# 01_POWER.net
KiCad netlist of a schematic drawn in Altium Designer
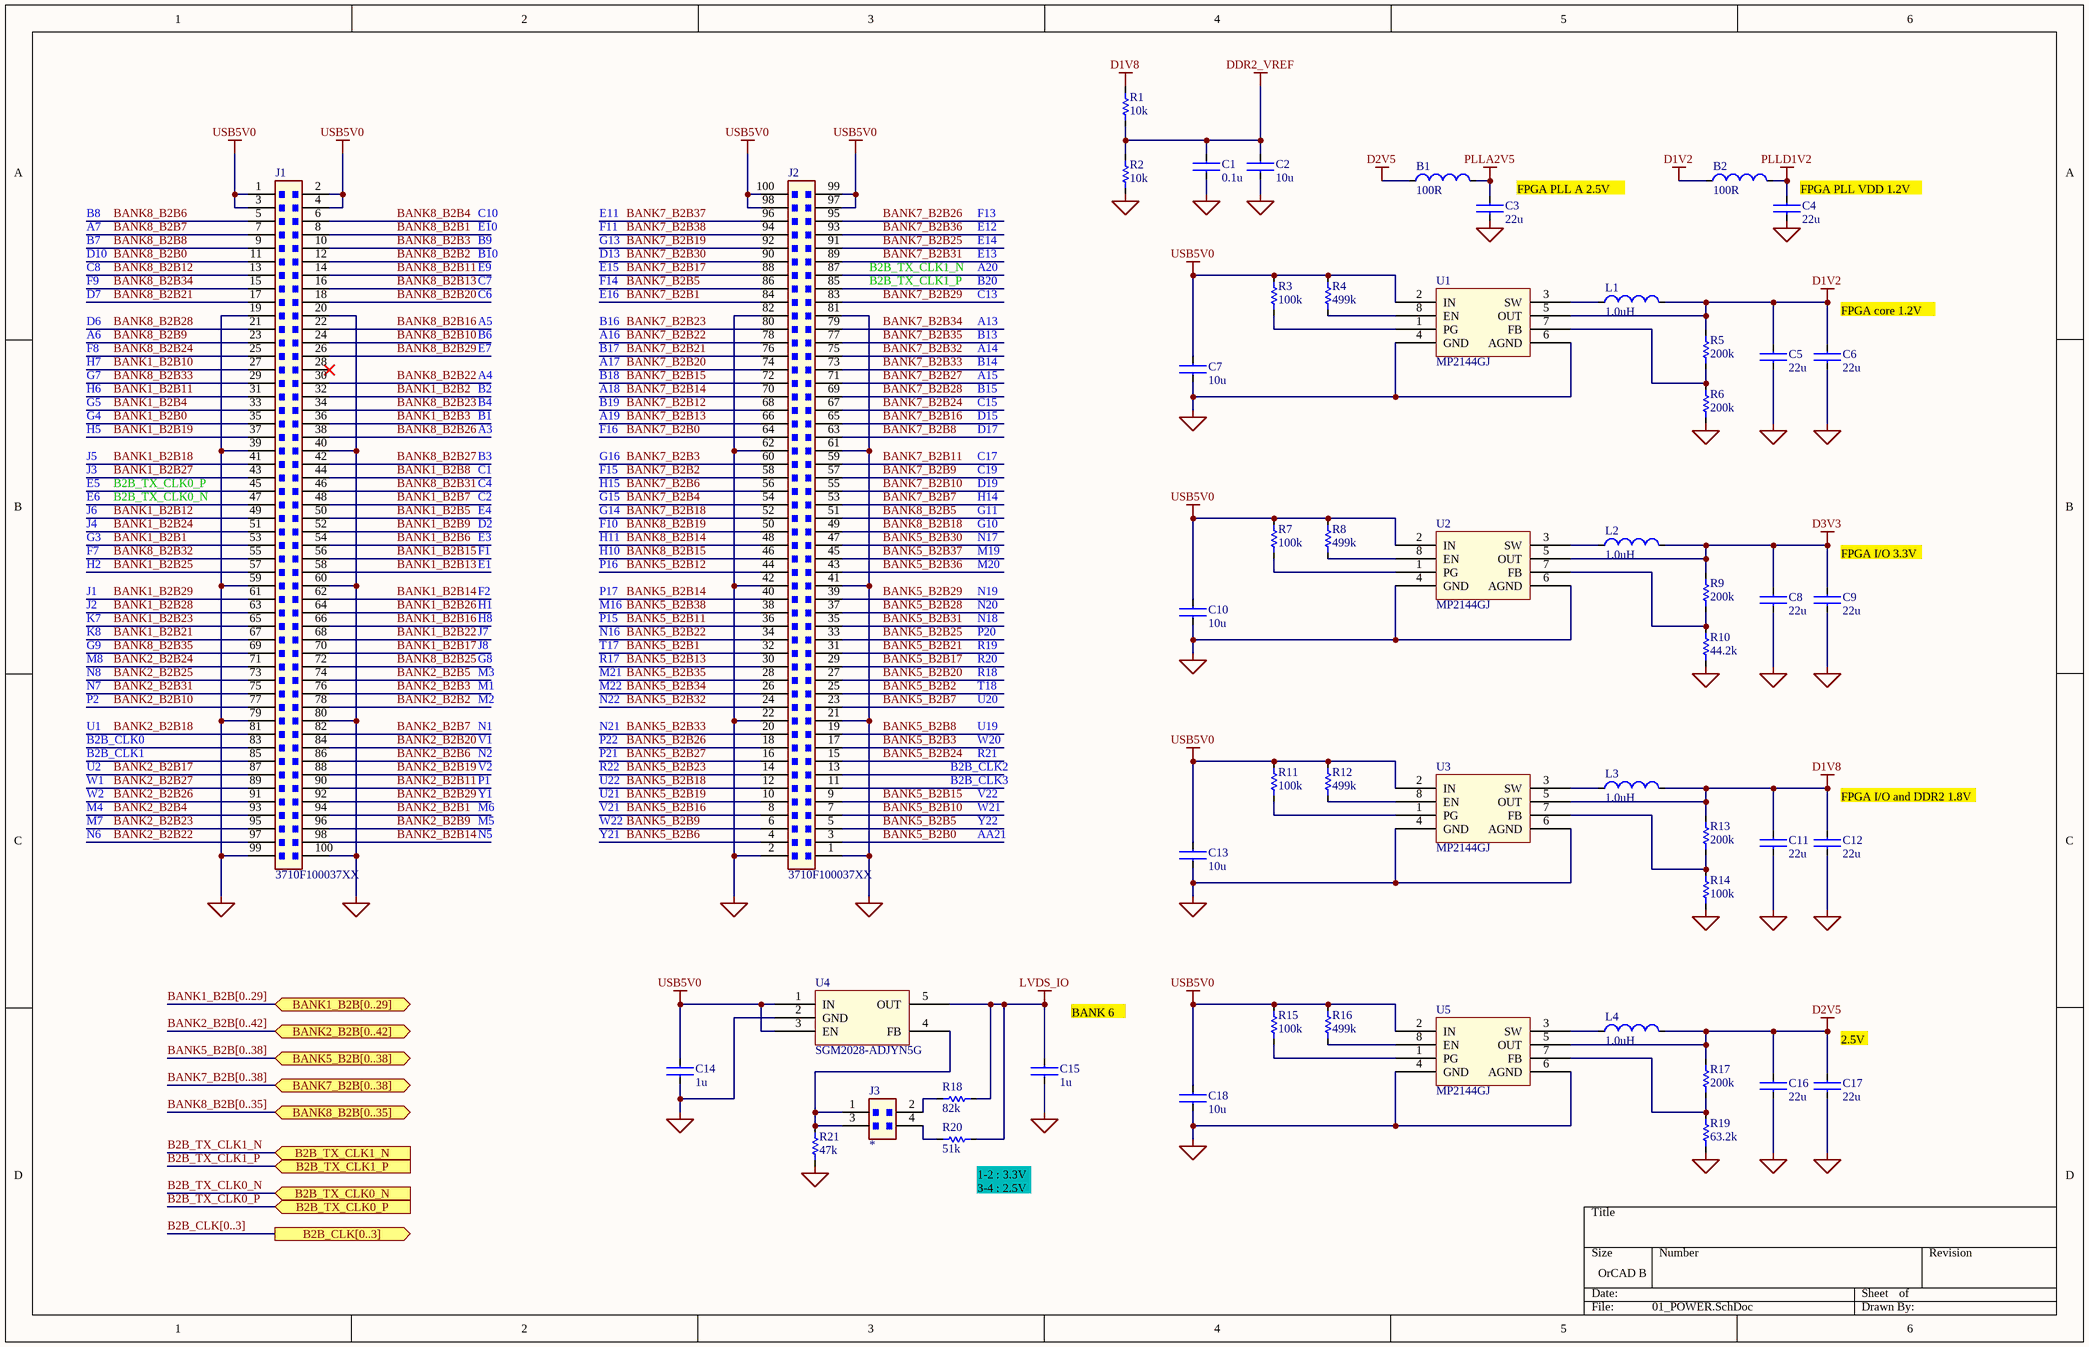
[diagram p0: 01_POWER.SchDoc]

(export (version "E")
  (design (tool "Eeschema 10.0.6"))
  (components
    (comp (ref "B1")
      (value "100R")
      (footprint "INDC1608X09N_B0603_TAIYO")
      (description "Bead,100R,2500mA,0.035ohm,0603")
      (libsource (lib "AD15_libpkg") (part "FBMH1608HM101-T"))
    )
    (comp (ref "B2")
      (value "100R")
      (footprint "INDC1608X09N_B0603_TAIYO")
      (description "Bead,100R,2500mA,0.035ohm,0603")
      (libsource (lib "AD15_libpkg") (part "FBMH1608HM101-T"))
    )
    (comp (ref "C1")
      (value "0.1u")
      (footprint "C0402")
      (description "CAP,Ceramic,X7R,10%,16V,0.1uF,0402")
      (libsource (lib "C0402") (part "CAP011"))
    )
    (comp (ref "C2")
      (value "10u")
      (footprint "CAPC1608X09N_C0603")
      (description "CAP,Ceramic,X7R,10%,6.3V,10uF,0603")
      (libsource (lib "C0603") (part "CAP113"))
    )
    (comp (ref "C3")
      (value "22u")
      (footprint "CAPC1608X09N_C0603")
      (description "CAP,Ceramic,X7R,10%,6.3V,22uF,0603")
      (libsource (lib "C0603") (part "CAP114"))
    )
    (comp (ref "C4")
      (value "22u")
      (footprint "CAPC1608X09N_C0603")
      (description "CAP,Ceramic,X7R,10%,6.3V,22uF,0603")
      (libsource (lib "C0603") (part "CAP114"))
    )
    (comp (ref "C5")
      (value "22u")
      (footprint "CAPC1608X09N_C0603")
      (description "CAP,Ceramic,X7R,10%,6.3V,22uF,0603")
      (libsource (lib "C0603") (part "CAP114"))
    )
    (comp (ref "C6")
      (value "22u")
      (footprint "CAPC1608X09N_C0603")
      (description "CAP,Ceramic,X7R,10%,6.3V,22uF,0603")
      (libsource (lib "C0603") (part "CAP114"))
    )
    (comp (ref "C7")
      (value "10u")
      (footprint "CAPC1608X09N_C0603")
      (description "CAP,Ceramic,X7R,10%,6.3V,10uF,0603")
      (libsource (lib "C0603") (part "CAP113"))
    )
    (comp (ref "C8")
      (value "22u")
      (footprint "CAPC1608X09N_C0603")
      (description "CAP,Ceramic,X7R,10%,6.3V,22uF,0603")
      (libsource (lib "C0603") (part "CAP114"))
    )
    (comp (ref "C9")
      (value "22u")
      (footprint "CAPC1608X09N_C0603")
      (description "CAP,Ceramic,X7R,10%,6.3V,22uF,0603")
      (libsource (lib "C0603") (part "CAP114"))
    )
    (comp (ref "C10")
      (value "10u")
      (footprint "CAPC1608X09N_C0603")
      (description "CAP,Ceramic,X7R,10%,6.3V,10uF,0603")
      (libsource (lib "C0603") (part "CAP113"))
    )
    (comp (ref "C11")
      (value "22u")
      (footprint "CAPC1608X09N_C0603")
      (description "CAP,Ceramic,X7R,10%,6.3V,22uF,0603")
      (libsource (lib "C0603") (part "CAP114"))
    )
    (comp (ref "C12")
      (value "22u")
      (footprint "CAPC1608X09N_C0603")
      (description "CAP,Ceramic,X7R,10%,6.3V,22uF,0603")
      (libsource (lib "C0603") (part "CAP114"))
    )
    (comp (ref "C13")
      (value "10u")
      (footprint "CAPC1608X09N_C0603")
      (description "CAP,Ceramic,X7R,10%,6.3V,10uF,0603")
      (libsource (lib "C0603") (part "CAP113"))
    )
    (comp (ref "C14")
      (value "1u")
      (footprint "CAPC1608X09N_C0603")
      (description "CAP,Ceramic,X7R,10%,16V,1uF,0603")
      (libsource (lib "AD15_libpkg") (part "CAP12"))
    )
    (comp (ref "C15")
      (value "1u")
      (footprint "CAPC1608X09N_C0603")
      (description "CAP,Ceramic,X7R,10%,16V,1uF,0603")
      (libsource (lib "AD15_libpkg") (part "CAP12"))
    )
    (comp (ref "C16")
      (value "22u")
      (footprint "CAPC1608X09N_C0603")
      (description "CAP,Ceramic,X7R,10%,6.3V,22uF,0603")
      (libsource (lib "C0603") (part "CAP114"))
    )
    (comp (ref "C17")
      (value "22u")
      (footprint "CAPC1608X09N_C0603")
      (description "CAP,Ceramic,X7R,10%,6.3V,22uF,0603")
      (libsource (lib "C0603") (part "CAP114"))
    )
    (comp (ref "C18")
      (value "10u")
      (footprint "CAPC1608X09N_C0603")
      (description "CAP,Ceramic,X7R,10%,6.3V,10uF,0603")
      (libsource (lib "C0603") (part "CAP113"))
    )
    (comp (ref "J1")
      (value "3710F100037XX")
      (footprint "3710F100037XX")
      (description "B2B female,100Pin,Vertical,0.8mm Pitch,SMD")
      (libsource (lib "AD15_schlib") (part "3710F100037XX"))
    )
    (comp (ref "J2")
      (value "3710F100037XX")
      (footprint "3710F100037XX")
      (description "B2B female,100Pin,Vertical,0.8mm Pitch,SMD")
      (libsource (lib "AD15_schlib") (part "3710F100037XX"))
    )
    (comp (ref "J3")
      (value "*")
      (footprint "334202XX30000")
      (description "Header,4Pin,Vertical,1.27mm Pitch,SMD")
      (libsource (lib "AD15_schlib") (part "334202XX30000"))
    )
    (comp (ref "L1")
      (value "1.0uH")
      (footprint "NR3015T1R0N")
      (description "Inductor,1.0uH,2100mA,0.03ohm,SMD")
      (libsource (lib "AD15_schlib") (part "NR3015T1R0N"))
    )
    (comp (ref "L2")
      (value "1.0uH")
      (footprint "NR3015T1R0N")
      (description "Inductor,1.0uH,2100mA,0.03ohm,SMD")
      (libsource (lib "AD15_schlib") (part "NR3015T1R0N"))
    )
    (comp (ref "L3")
      (value "1.0uH")
      (footprint "NR3015T1R0N")
      (description "Inductor,1.0uH,2100mA,0.03ohm,SMD")
      (libsource (lib "AD15_schlib") (part "NR3015T1R0N"))
    )
    (comp (ref "L4")
      (value "1.0uH")
      (footprint "NR3015T1R0N")
      (description "Inductor,1.0uH,2100mA,0.03ohm,SMD")
      (libsource (lib "AD15_schlib") (part "NR3015T1R0N"))
    )
    (comp (ref "R1")
      (value "10k")
      (footprint "R0402")
      (description "RES,10k,1%,1/16W,0402")
      (libsource (lib "R0402") (part "RES012"))
    )
    (comp (ref "R2")
      (value "10k")
      (footprint "R0402")
      (description "RES,10k,1%,1/16W,0402")
      (libsource (lib "R0402") (part "RES012"))
    )
    (comp (ref "R3")
      (value "100k")
      (footprint "R0402")
      (description "RES,100k,1%,1/16W,0402")
      (libsource (lib "R0402") (part "RES013"))
    )
    (comp (ref "R4")
      (value "499k")
      (footprint "R0402")
      (description "RES,499k,1%,1/16W,0402")
      (libsource (lib "R0402") (part "RES0117_1"))
    )
    (comp (ref "R5")
      (value "200k")
      (footprint "R0402")
      (description "RES,200k,1%,1/16W,0402")
      (libsource (lib "R0402") (part "RES0117"))
    )
    (comp (ref "R6")
      (value "200k")
      (footprint "R0402")
      (description "RES,200k,1%,1/16W,0402")
      (libsource (lib "R0402") (part "RES0117"))
    )
    (comp (ref "R7")
      (value "100k")
      (footprint "R0402")
      (description "RES,100k,1%,1/16W,0402")
      (libsource (lib "R0402") (part "RES013"))
    )
    (comp (ref "R8")
      (value "499k")
      (footprint "R0402")
      (description "RES,499k,1%,1/16W,0402")
      (libsource (lib "R0402") (part "RES0117_1"))
    )
    (comp (ref "R9")
      (value "200k")
      (footprint "R0402")
      (description "RES,200k,1%,1/16W,0402")
      (libsource (lib "R0402") (part "RES0117"))
    )
    (comp (ref "R10")
      (value "44.2k")
      (footprint "R0402")
      (description "RES,44.2k,1%,1/16W,0402")
      (libsource (lib "R0402") (part "RES0124_1"))
    )
    (comp (ref "R11")
      (value "100k")
      (footprint "R0402")
      (description "RES,100k,1%,1/16W,0402")
      (libsource (lib "R0402") (part "RES013"))
    )
    (comp (ref "R12")
      (value "499k")
      (footprint "R0402")
      (description "RES,499k,1%,1/16W,0402")
      (libsource (lib "R0402") (part "RES0117_1"))
    )
    (comp (ref "R13")
      (value "200k")
      (footprint "R0402")
      (description "RES,200k,1%,1/16W,0402")
      (libsource (lib "R0402") (part "RES0117"))
    )
    (comp (ref "R14")
      (value "100k")
      (footprint "R0402")
      (description "RES,100k,1%,1/16W,0402")
      (libsource (lib "R0402") (part "RES013"))
    )
    (comp (ref "R15")
      (value "100k")
      (footprint "R0402")
      (description "RES,100k,1%,1/16W,0402")
      (libsource (lib "R0402") (part "RES013"))
    )
    (comp (ref "R16")
      (value "499k")
      (footprint "R0402")
      (description "RES,499k,1%,1/16W,0402")
      (libsource (lib "R0402") (part "RES0117_1"))
    )
    (comp (ref "R17")
      (value "200k")
      (footprint "R0402")
      (description "RES,200k,1%,1/16W,0402")
      (libsource (lib "R0402") (part "RES0117"))
    )
    (comp (ref "R18")
      (value "82k")
      (footprint "R0402")
      (description "RES,82k,1%,1/16W,0402")
      (libsource (lib "AD15_libpkg") (part "RES0123_1"))
    )
    (comp (ref "R19")
      (value "63.2k")
      (footprint "R0402")
      (description "RES,63.2k,1%,1/16W,0402")
      (libsource (lib "R0402") (part "RES0126_1"))
    )
    (comp (ref "R20")
      (value "51k")
      (footprint "R0402")
      (description "RES,51k,1%,1/16W,0402")
      (libsource (lib "AD15_libpkg") (part "RES014_1"))
    )
    (comp (ref "R21")
      (value "47k")
      (footprint "R0402")
      (description "RES,47k,1%,1/16W,0402")
      (libsource (lib "AD15_libpkg") (part "RES0127"))
    )
    (comp (ref "U1")
      (value "MP2144GJ")
      (footprint "TSOT23-8_MP2144GJ")
      (description "IC,DC/DC,2A,1.2MHz,TSOT23-8")
      (libsource (lib "AD15_schlib") (part "MP2144GJ"))
    )
    (comp (ref "U2")
      (value "MP2144GJ")
      (footprint "TSOT23-8_MP2144GJ")
      (description "IC,DC/DC,2A,1.2MHz,TSOT23-8")
      (libsource (lib "AD15_schlib") (part "MP2144GJ"))
    )
    (comp (ref "U3")
      (value "MP2144GJ")
      (footprint "TSOT23-8_MP2144GJ")
      (description "IC,DC/DC,2A,1.2MHz,TSOT23-8")
      (libsource (lib "AD15_schlib") (part "MP2144GJ"))
    )
    (comp (ref "U4")
      (value "SGM2028-ADJYN5G")
      (footprint "SOT95P280X125-5N_SGM2028")
      (description "IC,LDO 500mA,Adjustable,SOT23-5")
      (libsource (lib "AD15_libpkg") (part "SGM2028-ADJ"))
    )
    (comp (ref "U5")
      (value "MP2144GJ")
      (footprint "TSOT23-8_MP2144GJ")
      (description "IC,DC/DC,2A,1.2MHz,TSOT23-8")
      (libsource (lib "AD15_schlib") (part "MP2144GJ"))
    )
  )
  (nets
    (net (code "25") (name "/A20") (class "Default")
      (node (ref "J2") (pin "87") (pinfunction "87_87") (pintype "passive"))
    )
    (net (code "26") (name "/B2B_CLK0") (class "Default")
      (node (ref "J1") (pin "83") (pinfunction "83_83") (pintype "passive"))
    )
    (net (code "27") (name "/B2B_CLK1") (class "Default")
      (node (ref "J1") (pin "85") (pinfunction "85_85") (pintype "passive"))
    )
    (net (code "28") (name "/B2B_CLK2") (class "Default")
      (node (ref "J2") (pin "13") (pinfunction "13_13") (pintype "passive"))
    )
    (net (code "29") (name "/B2B_CLK3") (class "Default")
      (node (ref "J2") (pin "11") (pinfunction "11_11") (pintype "passive"))
    )
    (net (code "31") (name "/B2B_TX_CLK0_N") (class "Default")
      (node (ref "J1") (pin "47") (pinfunction "47_47") (pintype "passive"))
    )
    (net (code "32") (name "/B2B_TX_CLK0_P") (class "Default")
      (node (ref "J1") (pin "45") (pinfunction "45_45") (pintype "passive"))
    )
    (net (code "33") (name "/B20") (class "Default")
      (node (ref "J2") (pin "85") (pinfunction "85_85") (pintype "passive"))
    )
    (net (code "34") (name "/BANK1_B2B0") (class "Default")
      (node (ref "J1") (pin "35") (pinfunction "35_35") (pintype "passive"))
    )
    (net (code "35") (name "/BANK1_B2B1") (class "Default")
      (node (ref "J1") (pin "53") (pinfunction "53_53") (pintype "passive"))
    )
    (net (code "36") (name "/BANK1_B2B2") (class "Default")
      (node (ref "J1") (pin "32") (pinfunction "32_32") (pintype "passive"))
    )
    (net (code "37") (name "/BANK1_B2B3") (class "Default")
      (node (ref "J1") (pin "36") (pinfunction "36_36") (pintype "passive"))
    )
    (net (code "38") (name "/BANK1_B2B4") (class "Default")
      (node (ref "J1") (pin "33") (pinfunction "33_33") (pintype "passive"))
    )
    (net (code "39") (name "/BANK1_B2B5") (class "Default")
      (node (ref "J1") (pin "50") (pinfunction "50_50") (pintype "passive"))
    )
    (net (code "40") (name "/BANK1_B2B6") (class "Default")
      (node (ref "J1") (pin "54") (pinfunction "54_54") (pintype "passive"))
    )
    (net (code "41") (name "/BANK1_B2B7") (class "Default")
      (node (ref "J1") (pin "48") (pinfunction "48_48") (pintype "passive"))
    )
    (net (code "42") (name "/BANK1_B2B8") (class "Default")
      (node (ref "J1") (pin "44") (pinfunction "44_44") (pintype "passive"))
    )
    (net (code "43") (name "/BANK1_B2B9") (class "Default")
      (node (ref "J1") (pin "52") (pinfunction "52_52") (pintype "passive"))
    )
    (net (code "44") (name "/BANK1_B2B10") (class "Default")
      (node (ref "J1") (pin "27") (pinfunction "27_27") (pintype "passive"))
    )
    (net (code "45") (name "/BANK1_B2B11") (class "Default")
      (node (ref "J1") (pin "31") (pinfunction "31_31") (pintype "passive"))
    )
    (net (code "46") (name "/BANK1_B2B12") (class "Default")
      (node (ref "J1") (pin "49") (pinfunction "49_49") (pintype "passive"))
    )
    (net (code "47") (name "/BANK1_B2B13") (class "Default")
      (node (ref "J1") (pin "58") (pinfunction "58_58") (pintype "passive"))
    )
    (net (code "48") (name "/BANK1_B2B14") (class "Default")
      (node (ref "J1") (pin "62") (pinfunction "62_62") (pintype "passive"))
    )
    (net (code "49") (name "/BANK1_B2B15") (class "Default")
      (node (ref "J1") (pin "56") (pinfunction "56_56") (pintype "passive"))
    )
    (net (code "50") (name "/BANK1_B2B16") (class "Default")
      (node (ref "J1") (pin "66") (pinfunction "66_66") (pintype "passive"))
    )
    (net (code "51") (name "/BANK1_B2B17") (class "Default")
      (node (ref "J1") (pin "70") (pinfunction "70_70") (pintype "passive"))
    )
    (net (code "52") (name "/BANK1_B2B18") (class "Default")
      (node (ref "J1") (pin "41") (pinfunction "41_41") (pintype "passive"))
    )
    (net (code "53") (name "/BANK1_B2B19") (class "Default")
      (node (ref "J1") (pin "37") (pinfunction "37_37") (pintype "passive"))
    )
    (net (code "54") (name "/BANK1_B2B21") (class "Default")
      (node (ref "J1") (pin "67") (pinfunction "67_67") (pintype "passive"))
    )
    (net (code "55") (name "/BANK1_B2B22") (class "Default")
      (node (ref "J1") (pin "68") (pinfunction "68_68") (pintype "passive"))
    )
    (net (code "56") (name "/BANK1_B2B23") (class "Default")
      (node (ref "J1") (pin "65") (pinfunction "65_65") (pintype "passive"))
    )
    (net (code "57") (name "/BANK1_B2B24") (class "Default")
      (node (ref "J1") (pin "51") (pinfunction "51_51") (pintype "passive"))
    )
    (net (code "58") (name "/BANK1_B2B25") (class "Default")
      (node (ref "J1") (pin "57") (pinfunction "57_57") (pintype "passive"))
    )
    (net (code "59") (name "/BANK1_B2B26") (class "Default")
      (node (ref "J1") (pin "64") (pinfunction "64_64") (pintype "passive"))
    )
    (net (code "60") (name "/BANK1_B2B27") (class "Default")
      (node (ref "J1") (pin "43") (pinfunction "43_43") (pintype "passive"))
    )
    (net (code "61") (name "/BANK1_B2B28") (class "Default")
      (node (ref "J1") (pin "63") (pinfunction "63_63") (pintype "passive"))
    )
    (net (code "62") (name "/BANK1_B2B29") (class "Default")
      (node (ref "J1") (pin "61") (pinfunction "61_61") (pintype "passive"))
    )
    (net (code "64") (name "/BANK2_B2B1") (class "Default")
      (node (ref "J1") (pin "94") (pinfunction "94_94") (pintype "passive"))
    )
    (net (code "65") (name "/BANK2_B2B2") (class "Default")
      (node (ref "J1") (pin "78") (pinfunction "78_78") (pintype "passive"))
    )
    (net (code "66") (name "/BANK2_B2B3") (class "Default")
      (node (ref "J1") (pin "76") (pinfunction "76_76") (pintype "passive"))
    )
    (net (code "67") (name "/BANK2_B2B4") (class "Default")
      (node (ref "J1") (pin "93") (pinfunction "93_93") (pintype "passive"))
    )
    (net (code "68") (name "/BANK2_B2B5") (class "Default")
      (node (ref "J1") (pin "74") (pinfunction "74_74") (pintype "passive"))
    )
    (net (code "69") (name "/BANK2_B2B6") (class "Default")
      (node (ref "J1") (pin "86") (pinfunction "86_86") (pintype "passive"))
    )
    (net (code "70") (name "/BANK2_B2B7") (class "Default")
      (node (ref "J1") (pin "82") (pinfunction "82_82") (pintype "passive"))
    )
    (net (code "71") (name "/BANK2_B2B9") (class "Default")
      (node (ref "J1") (pin "96") (pinfunction "96_96") (pintype "passive"))
    )
    (net (code "72") (name "/BANK2_B2B10") (class "Default")
      (node (ref "J1") (pin "77") (pinfunction "77_77") (pintype "passive"))
    )
    (net (code "73") (name "/BANK2_B2B11") (class "Default")
      (node (ref "J1") (pin "90") (pinfunction "90_90") (pintype "passive"))
    )
    (net (code "74") (name "/BANK2_B2B14") (class "Default")
      (node (ref "J1") (pin "98") (pinfunction "98_98") (pintype "passive"))
    )
    (net (code "75") (name "/BANK2_B2B17") (class "Default")
      (node (ref "J1") (pin "87") (pinfunction "87_87") (pintype "passive"))
    )
    (net (code "76") (name "/BANK2_B2B18") (class "Default")
      (node (ref "J1") (pin "81") (pinfunction "81_81") (pintype "passive"))
    )
    (net (code "77") (name "/BANK2_B2B19") (class "Default")
      (node (ref "J1") (pin "88") (pinfunction "88_88") (pintype "passive"))
    )
    (net (code "78") (name "/BANK2_B2B20") (class "Default")
      (node (ref "J1") (pin "84") (pinfunction "84_84") (pintype "passive"))
    )
    (net (code "79") (name "/BANK2_B2B22") (class "Default")
      (node (ref "J1") (pin "97") (pinfunction "97_97") (pintype "passive"))
    )
    (net (code "80") (name "/BANK2_B2B23") (class "Default")
      (node (ref "J1") (pin "95") (pinfunction "95_95") (pintype "passive"))
    )
    (net (code "81") (name "/BANK2_B2B24") (class "Default")
      (node (ref "J1") (pin "71") (pinfunction "71_71") (pintype "passive"))
    )
    (net (code "82") (name "/BANK2_B2B25") (class "Default")
      (node (ref "J1") (pin "73") (pinfunction "73_73") (pintype "passive"))
    )
    (net (code "83") (name "/BANK2_B2B26") (class "Default")
      (node (ref "J1") (pin "91") (pinfunction "91_91") (pintype "passive"))
    )
    (net (code "84") (name "/BANK2_B2B27") (class "Default")
      (node (ref "J1") (pin "89") (pinfunction "89_89") (pintype "passive"))
    )
    (net (code "85") (name "/BANK2_B2B29") (class "Default")
      (node (ref "J1") (pin "92") (pinfunction "92_92") (pintype "passive"))
    )
    (net (code "86") (name "/BANK2_B2B31") (class "Default")
      (node (ref "J1") (pin "75") (pinfunction "75_75") (pintype "passive"))
    )
    (net (code "88") (name "/BANK5_B2B0") (class "Default")
      (node (ref "J2") (pin "3") (pinfunction "2_3") (pintype "passive"))
    )
    (net (code "89") (name "/BANK5_B2B1") (class "Default")
      (node (ref "J2") (pin "32") (pinfunction "32_32") (pintype "passive"))
    )
    (net (code "90") (name "/BANK5_B2B2") (class "Default")
      (node (ref "J2") (pin "25") (pinfunction "25_25") (pintype "passive"))
    )
    (net (code "91") (name "/BANK5_B2B3") (class "Default")
      (node (ref "J2") (pin "17") (pinfunction "17_17") (pintype "passive"))
    )
    (net (code "92") (name "/BANK5_B2B5") (class "Default")
      (node (ref "J2") (pin "5") (pinfunction "4_5") (pintype "passive"))
    )
    (net (code "93") (name "/BANK5_B2B6") (class "Default")
      (node (ref "J2") (pin "4") (pinfunction "3_4") (pintype "passive"))
    )
    (net (code "94") (name "/BANK5_B2B7") (class "Default")
      (node (ref "J2") (pin "23") (pinfunction "23_23") (pintype "passive"))
    )
    (net (code "95") (name "/BANK5_B2B8") (class "Default")
      (node (ref "J2") (pin "19") (pinfunction "19_19") (pintype "passive"))
    )
    (net (code "96") (name "/BANK5_B2B9") (class "Default")
      (node (ref "J2") (pin "6") (pinfunction "5_6") (pintype "passive"))
    )
    (net (code "97") (name "/BANK5_B2B10") (class "Default")
      (node (ref "J2") (pin "7") (pinfunction "6_7") (pintype "passive"))
    )
    (net (code "98") (name "/BANK5_B2B11") (class "Default")
      (node (ref "J2") (pin "36") (pinfunction "36_36") (pintype "passive"))
    )
    (net (code "99") (name "/BANK5_B2B12") (class "Default")
      (node (ref "J2") (pin "44") (pinfunction "44_44") (pintype "passive"))
    )
    (net (code "100") (name "/BANK5_B2B13") (class "Default")
      (node (ref "J2") (pin "30") (pinfunction "30_30") (pintype "passive"))
    )
    (net (code "101") (name "/BANK5_B2B14") (class "Default")
      (node (ref "J2") (pin "40") (pinfunction "40_40") (pintype "passive"))
    )
    (net (code "102") (name "/BANK5_B2B15") (class "Default")
      (node (ref "J2") (pin "9") (pinfunction "8_9") (pintype "passive"))
    )
    (net (code "103") (name "/BANK5_B2B16") (class "Default")
      (node (ref "J2") (pin "8") (pinfunction "7_8") (pintype "passive"))
    )
    (net (code "104") (name "/BANK5_B2B17") (class "Default")
      (node (ref "J2") (pin "29") (pinfunction "29_29") (pintype "passive"))
    )
    (net (code "105") (name "/BANK5_B2B18") (class "Default")
      (node (ref "J2") (pin "12") (pinfunction "12_12") (pintype "passive"))
    )
    (net (code "106") (name "/BANK5_B2B19") (class "Default")
      (node (ref "J2") (pin "10") (pinfunction "9_10") (pintype "passive"))
    )
    (net (code "107") (name "/BANK5_B2B20") (class "Default")
      (node (ref "J2") (pin "27") (pinfunction "27_27") (pintype "passive"))
    )
    (net (code "108") (name "/BANK5_B2B21") (class "Default")
      (node (ref "J2") (pin "31") (pinfunction "31_31") (pintype "passive"))
    )
    (net (code "109") (name "/BANK5_B2B22") (class "Default")
      (node (ref "J2") (pin "34") (pinfunction "34_34") (pintype "passive"))
    )
    (net (code "110") (name "/BANK5_B2B23") (class "Default")
      (node (ref "J2") (pin "14") (pinfunction "14_14") (pintype "passive"))
    )
    (net (code "111") (name "/BANK5_B2B24") (class "Default")
      (node (ref "J2") (pin "15") (pinfunction "15_15") (pintype "passive"))
    )
    (net (code "112") (name "/BANK5_B2B25") (class "Default")
      (node (ref "J2") (pin "33") (pinfunction "33_33") (pintype "passive"))
    )
    (net (code "113") (name "/BANK5_B2B26") (class "Default")
      (node (ref "J2") (pin "18") (pinfunction "18_18") (pintype "passive"))
    )
    (net (code "114") (name "/BANK5_B2B27") (class "Default")
      (node (ref "J2") (pin "16") (pinfunction "16_16") (pintype "passive"))
    )
    (net (code "115") (name "/BANK5_B2B28") (class "Default")
      (node (ref "J2") (pin "37") (pinfunction "37_37") (pintype "passive"))
    )
    (net (code "116") (name "/BANK5_B2B29") (class "Default")
      (node (ref "J2") (pin "39") (pinfunction "39_39") (pintype "passive"))
    )
    (net (code "117") (name "/BANK5_B2B30") (class "Default")
      (node (ref "J2") (pin "47") (pinfunction "47_47") (pintype "passive"))
    )
    (net (code "118") (name "/BANK5_B2B31") (class "Default")
      (node (ref "J2") (pin "35") (pinfunction "35_35") (pintype "passive"))
    )
    (net (code "119") (name "/BANK5_B2B32") (class "Default")
      (node (ref "J2") (pin "24") (pinfunction "24_24") (pintype "passive"))
    )
    (net (code "120") (name "/BANK5_B2B33") (class "Default")
      (node (ref "J2") (pin "20") (pinfunction "20_20") (pintype "passive"))
    )
    (net (code "121") (name "/BANK5_B2B34") (class "Default")
      (node (ref "J2") (pin "26") (pinfunction "26_26") (pintype "passive"))
    )
    (net (code "122") (name "/BANK5_B2B35") (class "Default")
      (node (ref "J2") (pin "28") (pinfunction "28_28") (pintype "passive"))
    )
    (net (code "123") (name "/BANK5_B2B36") (class "Default")
      (node (ref "J2") (pin "43") (pinfunction "43_43") (pintype "passive"))
    )
    (net (code "124") (name "/BANK5_B2B37") (class "Default")
      (node (ref "J2") (pin "45") (pinfunction "45_45") (pintype "passive"))
    )
    (net (code "125") (name "/BANK5_B2B38") (class "Default")
      (node (ref "J2") (pin "38") (pinfunction "38_38") (pintype "passive"))
    )
    (net (code "127") (name "/BANK7_B2B0") (class "Default")
      (node (ref "J2") (pin "64") (pinfunction "64_64") (pintype "passive"))
    )
    (net (code "128") (name "/BANK7_B2B1") (class "Default")
      (node (ref "J2") (pin "84") (pinfunction "84_84") (pintype "passive"))
    )
    (net (code "129") (name "/BANK7_B2B2") (class "Default")
      (node (ref "J2") (pin "58") (pinfunction "58_58") (pintype "passive"))
    )
    (net (code "130") (name "/BANK7_B2B3") (class "Default")
      (node (ref "J2") (pin "60") (pinfunction "60_60") (pintype "passive"))
    )
    (net (code "131") (name "/BANK7_B2B4") (class "Default")
      (node (ref "J2") (pin "54") (pinfunction "54_54") (pintype "passive"))
    )
    (net (code "132") (name "/BANK7_B2B5") (class "Default")
      (node (ref "J2") (pin "86") (pinfunction "86_86") (pintype "passive"))
    )
    (net (code "133") (name "/BANK7_B2B6") (class "Default")
      (node (ref "J2") (pin "56") (pinfunction "56_56") (pintype "passive"))
    )
    (net (code "134") (name "/BANK7_B2B7") (class "Default")
      (node (ref "J2") (pin "53") (pinfunction "53_53") (pintype "passive"))
    )
    (net (code "135") (name "/BANK7_B2B8") (class "Default")
      (node (ref "J2") (pin "63") (pinfunction "63_63") (pintype "passive"))
    )
    (net (code "136") (name "/BANK7_B2B9") (class "Default")
      (node (ref "J2") (pin "57") (pinfunction "57_57") (pintype "passive"))
    )
    (net (code "137") (name "/BANK7_B2B10") (class "Default")
      (node (ref "J2") (pin "55") (pinfunction "55_55") (pintype "passive"))
    )
    (net (code "138") (name "/BANK7_B2B11") (class "Default")
      (node (ref "J2") (pin "59") (pinfunction "59_59") (pintype "passive"))
    )
    (net (code "139") (name "/BANK7_B2B12") (class "Default")
      (node (ref "J2") (pin "68") (pinfunction "68_68") (pintype "passive"))
    )
    (net (code "140") (name "/BANK7_B2B13") (class "Default")
      (node (ref "J2") (pin "66") (pinfunction "66_66") (pintype "passive"))
    )
    (net (code "141") (name "/BANK7_B2B14") (class "Default")
      (node (ref "J2") (pin "70") (pinfunction "70_70") (pintype "passive"))
    )
    (net (code "142") (name "/BANK7_B2B15") (class "Default")
      (node (ref "J2") (pin "72") (pinfunction "72_72") (pintype "passive"))
    )
    (net (code "143") (name "/BANK7_B2B16") (class "Default")
      (node (ref "J2") (pin "65") (pinfunction "65_65") (pintype "passive"))
    )
    (net (code "144") (name "/BANK7_B2B17") (class "Default")
      (node (ref "J2") (pin "88") (pinfunction "88_88") (pintype "passive"))
    )
    (net (code "145") (name "/BANK7_B2B18") (class "Default")
      (node (ref "J2") (pin "52") (pinfunction "52_52") (pintype "passive"))
    )
    (net (code "146") (name "/BANK7_B2B19") (class "Default")
      (node (ref "J2") (pin "92") (pinfunction "92_92") (pintype "passive"))
    )
    (net (code "147") (name "/BANK7_B2B20") (class "Default")
      (node (ref "J2") (pin "74") (pinfunction "74_74") (pintype "passive"))
    )
    (net (code "148") (name "/BANK7_B2B21") (class "Default")
      (node (ref "J2") (pin "76") (pinfunction "76_76") (pintype "passive"))
    )
    (net (code "149") (name "/BANK7_B2B22") (class "Default")
      (node (ref "J2") (pin "78") (pinfunction "78_78") (pintype "passive"))
    )
    (net (code "150") (name "/BANK7_B2B23") (class "Default")
      (node (ref "J2") (pin "80") (pinfunction "80_80") (pintype "passive"))
    )
    (net (code "151") (name "/BANK7_B2B24") (class "Default")
      (node (ref "J2") (pin "67") (pinfunction "67_67") (pintype "passive"))
    )
    (net (code "152") (name "/BANK7_B2B25") (class "Default")
      (node (ref "J2") (pin "91") (pinfunction "91_91") (pintype "passive"))
    )
    (net (code "153") (name "/BANK7_B2B26") (class "Default")
      (node (ref "J2") (pin "95") (pinfunction "95_95") (pintype "passive"))
    )
    (net (code "154") (name "/BANK7_B2B27") (class "Default")
      (node (ref "J2") (pin "71") (pinfunction "71_71") (pintype "passive"))
    )
    (net (code "155") (name "/BANK7_B2B28") (class "Default")
      (node (ref "J2") (pin "69") (pinfunction "69_69") (pintype "passive"))
    )
    (net (code "156") (name "/BANK7_B2B29") (class "Default")
      (node (ref "J2") (pin "83") (pinfunction "83_83") (pintype "passive"))
    )
    (net (code "157") (name "/BANK7_B2B30") (class "Default")
      (node (ref "J2") (pin "90") (pinfunction "90_90") (pintype "passive"))
    )
    (net (code "158") (name "/BANK7_B2B31") (class "Default")
      (node (ref "J2") (pin "89") (pinfunction "89_89") (pintype "passive"))
    )
    (net (code "159") (name "/BANK7_B2B32") (class "Default")
      (node (ref "J2") (pin "75") (pinfunction "75_75") (pintype "passive"))
    )
    (net (code "160") (name "/BANK7_B2B33") (class "Default")
      (node (ref "J2") (pin "73") (pinfunction "73_73") (pintype "passive"))
    )
    (net (code "161") (name "/BANK7_B2B34") (class "Default")
      (node (ref "J2") (pin "79") (pinfunction "79_79") (pintype "passive"))
    )
    (net (code "162") (name "/BANK7_B2B35") (class "Default")
      (node (ref "J2") (pin "77") (pinfunction "77_77") (pintype "passive"))
    )
    (net (code "163") (name "/BANK7_B2B36") (class "Default")
      (node (ref "J2") (pin "93") (pinfunction "93_93") (pintype "passive"))
    )
    (net (code "164") (name "/BANK7_B2B37") (class "Default")
      (node (ref "J2") (pin "96") (pinfunction "96_96") (pintype "passive"))
    )
    (net (code "165") (name "/BANK7_B2B38") (class "Default")
      (node (ref "J2") (pin "94") (pinfunction "94_94") (pintype "passive"))
    )
    (net (code "167") (name "/BANK8_B2B0") (class "Default")
      (node (ref "J1") (pin "11") (pinfunction "11_11") (pintype "passive"))
    )
    (net (code "168") (name "/BANK8_B2B1") (class "Default")
      (node (ref "J1") (pin "8") (pinfunction "7_8") (pintype "passive"))
    )
    (net (code "169") (name "/BANK8_B2B2") (class "Default")
      (node (ref "J1") (pin "12") (pinfunction "12_12") (pintype "passive"))
    )
    (net (code "170") (name "/BANK8_B2B3") (class "Default")
      (node (ref "J1") (pin "10") (pinfunction "9_10") (pintype "passive"))
    )
    (net (code "171") (name "/BANK8_B2B4") (class "Default")
      (node (ref "J1") (pin "6") (pinfunction "5_6") (pintype "passive"))
    )
    (net (code "172") (name "/BANK8_B2B5") (class "Default")
      (node (ref "J2") (pin "51") (pinfunction "51_51") (pintype "passive"))
    )
    (net (code "173") (name "/BANK8_B2B6") (class "Default")
      (node (ref "J1") (pin "5") (pinfunction "4_5") (pintype "passive"))
    )
    (net (code "174") (name "/BANK8_B2B7") (class "Default")
      (node (ref "J1") (pin "7") (pinfunction "6_7") (pintype "passive"))
    )
    (net (code "175") (name "/BANK8_B2B8") (class "Default")
      (node (ref "J1") (pin "9") (pinfunction "8_9") (pintype "passive"))
    )
    (net (code "176") (name "/BANK8_B2B9") (class "Default")
      (node (ref "J1") (pin "23") (pinfunction "23_23") (pintype "passive"))
    )
    (net (code "177") (name "/BANK8_B2B10") (class "Default")
      (node (ref "J1") (pin "24") (pinfunction "24_24") (pintype "passive"))
    )
    (net (code "178") (name "/BANK8_B2B11") (class "Default")
      (node (ref "J1") (pin "14") (pinfunction "14_14") (pintype "passive"))
    )
    (net (code "179") (name "/BANK8_B2B12") (class "Default")
      (node (ref "J1") (pin "13") (pinfunction "13_13") (pintype "passive"))
    )
    (net (code "180") (name "/BANK8_B2B13") (class "Default")
      (node (ref "J1") (pin "16") (pinfunction "16_16") (pintype "passive"))
    )
    (net (code "181") (name "/BANK8_B2B14") (class "Default")
      (node (ref "J2") (pin "48") (pinfunction "48_48") (pintype "passive"))
    )
    (net (code "182") (name "/BANK8_B2B15") (class "Default")
      (node (ref "J2") (pin "46") (pinfunction "46_46") (pintype "passive"))
    )
    (net (code "183") (name "/BANK8_B2B16") (class "Default")
      (node (ref "J1") (pin "22") (pinfunction "22_22") (pintype "passive"))
    )
    (net (code "184") (name "/BANK8_B2B18") (class "Default")
      (node (ref "J2") (pin "49") (pinfunction "49_49") (pintype "passive"))
    )
    (net (code "185") (name "/BANK8_B2B19") (class "Default")
      (node (ref "J2") (pin "50") (pinfunction "50_50") (pintype "passive"))
    )
    (net (code "186") (name "/BANK8_B2B20") (class "Default")
      (node (ref "J1") (pin "18") (pinfunction "18_18") (pintype "passive"))
    )
    (net (code "187") (name "/BANK8_B2B21") (class "Default")
      (node (ref "J1") (pin "17") (pinfunction "17_17") (pintype "passive"))
    )
    (net (code "188") (name "/BANK8_B2B22") (class "Default")
      (node (ref "J1") (pin "30") (pinfunction "30_30") (pintype "passive"))
    )
    (net (code "189") (name "/BANK8_B2B23") (class "Default")
      (node (ref "J1") (pin "34") (pinfunction "34_34") (pintype "passive"))
    )
    (net (code "190") (name "/BANK8_B2B24") (class "Default")
      (node (ref "J1") (pin "25") (pinfunction "25_25") (pintype "passive"))
    )
    (net (code "191") (name "/BANK8_B2B25") (class "Default")
      (node (ref "J1") (pin "72") (pinfunction "72_72") (pintype "passive"))
    )
    (net (code "192") (name "/BANK8_B2B26") (class "Default")
      (node (ref "J1") (pin "38") (pinfunction "38_38") (pintype "passive"))
    )
    (net (code "193") (name "/BANK8_B2B27") (class "Default")
      (node (ref "J1") (pin "42") (pinfunction "42_42") (pintype "passive"))
    )
    (net (code "194") (name "/BANK8_B2B28") (class "Default")
      (node (ref "J1") (pin "21") (pinfunction "21_21") (pintype "passive"))
    )
    (net (code "195") (name "/BANK8_B2B29") (class "Default")
      (node (ref "J1") (pin "26") (pinfunction "26_26") (pintype "passive"))
    )
    (net (code "196") (name "/BANK8_B2B31") (class "Default")
      (node (ref "J1") (pin "46") (pinfunction "46_46") (pintype "passive"))
    )
    (net (code "197") (name "/BANK8_B2B32") (class "Default")
      (node (ref "J1") (pin "55") (pinfunction "55_55") (pintype "passive"))
    )
    (net (code "198") (name "/BANK8_B2B33") (class "Default")
      (node (ref "J1") (pin "29") (pinfunction "29_29") (pintype "passive"))
    )
    (net (code "199") (name "/BANK8_B2B34") (class "Default")
      (node (ref "J1") (pin "15") (pinfunction "15_15") (pintype "passive"))
    )
    (net (code "200") (name "/BANK8_B2B35") (class "Default")
      (node (ref "J1") (pin "69") (pinfunction "69_69") (pintype "passive"))
    )
    (net (code "202") (name "D1V2") (class "Default")
      (node (ref "B2") (pin "2") (pinfunction "1_2") (pintype "passive"))
      (node (ref "C5") (pin "1") (pinfunction "0_1") (pintype "passive"))
      (node (ref "C6") (pin "1") (pinfunction "0_1") (pintype "passive"))
      (node (ref "L1") (pin "1") (pinfunction "0_1") (pintype "passive"))
      (node (ref "R5") (pin "2") (pinfunction "2_2") (pintype "passive"))
      (node (ref "U1") (pin "5") (pinfunction "OUT_5") (pintype "power_in"))
    )
    (net (code "203") (name "D1V8") (class "Default")
      (node (ref "C11") (pin "1") (pinfunction "0_1") (pintype "passive"))
      (node (ref "C12") (pin "1") (pinfunction "0_1") (pintype "passive"))
      (node (ref "L3") (pin "1") (pinfunction "0_1") (pintype "passive"))
      (node (ref "R1") (pin "2") (pinfunction "2_2") (pintype "passive"))
      (node (ref "R13") (pin "2") (pinfunction "2_2") (pintype "passive"))
      (node (ref "U3") (pin "5") (pinfunction "OUT_5") (pintype "power_in"))
    )
    (net (code "204") (name "D2V5") (class "Default")
      (node (ref "B1") (pin "2") (pinfunction "1_2") (pintype "passive"))
      (node (ref "C16") (pin "1") (pinfunction "0_1") (pintype "passive"))
      (node (ref "C17") (pin "1") (pinfunction "0_1") (pintype "passive"))
      (node (ref "L4") (pin "1") (pinfunction "0_1") (pintype "passive"))
      (node (ref "R17") (pin "2") (pinfunction "2_2") (pintype "passive"))
      (node (ref "U5") (pin "5") (pinfunction "OUT_5") (pintype "power_in"))
    )
    (net (code "205") (name "D3V3") (class "Default")
      (node (ref "C8") (pin "1") (pinfunction "0_1") (pintype "passive"))
      (node (ref "C9") (pin "1") (pinfunction "0_1") (pintype "passive"))
      (node (ref "L2") (pin "1") (pinfunction "0_1") (pintype "passive"))
      (node (ref "R9") (pin "2") (pinfunction "2_2") (pintype "passive"))
      (node (ref "U2") (pin "5") (pinfunction "OUT_5") (pintype "power_in"))
    )
    (net (code "206") (name "DDR2_VREF") (class "Default")
      (node (ref "C1") (pin "1") (pinfunction "0_1") (pintype "passive"))
      (node (ref "C2") (pin "1") (pinfunction "0_1") (pintype "passive"))
      (node (ref "R1") (pin "1") (pinfunction "0_1") (pintype "passive"))
      (node (ref "R2") (pin "2") (pinfunction "2_2") (pintype "passive"))
    )
    (net (code "207") (name "GND") (class "Default")
      (node (ref "C1") (pin "2") (pinfunction "1_2") (pintype "passive"))
      (node (ref "C10") (pin "2") (pinfunction "1_2") (pintype "passive"))
      (node (ref "C11") (pin "2") (pinfunction "1_2") (pintype "passive"))
      (node (ref "C12") (pin "2") (pinfunction "1_2") (pintype "passive"))
      (node (ref "C13") (pin "2") (pinfunction "1_2") (pintype "passive"))
      (node (ref "C14") (pin "2") (pinfunction "1_2") (pintype "passive"))
      (node (ref "C15") (pin "2") (pinfunction "1_2") (pintype "passive"))
      (node (ref "C16") (pin "2") (pinfunction "1_2") (pintype "passive"))
      (node (ref "C17") (pin "2") (pinfunction "1_2") (pintype "passive"))
      (node (ref "C18") (pin "2") (pinfunction "1_2") (pintype "passive"))
      (node (ref "C2") (pin "2") (pinfunction "1_2") (pintype "passive"))
      (node (ref "C3") (pin "2") (pinfunction "1_2") (pintype "passive"))
      (node (ref "C4") (pin "2") (pinfunction "1_2") (pintype "passive"))
      (node (ref "C5") (pin "2") (pinfunction "1_2") (pintype "passive"))
      (node (ref "C6") (pin "2") (pinfunction "1_2") (pintype "passive"))
      (node (ref "C7") (pin "2") (pinfunction "1_2") (pintype "passive"))
      (node (ref "C8") (pin "2") (pinfunction "1_2") (pintype "passive"))
      (node (ref "C9") (pin "2") (pinfunction "1_2") (pintype "passive"))
      (node (ref "J1") (pin "100") (pinfunction "100_100") (pintype "passive"))
      (node (ref "J1") (pin "19") (pinfunction "19_19") (pintype "passive"))
      (node (ref "J1") (pin "20") (pinfunction "20_20") (pintype "passive"))
      (node (ref "J1") (pin "39") (pinfunction "39_39") (pintype "passive"))
      (node (ref "J1") (pin "40") (pinfunction "40_40") (pintype "passive"))
      (node (ref "J1") (pin "59") (pinfunction "59_59") (pintype "passive"))
      (node (ref "J1") (pin "60") (pinfunction "60_60") (pintype "passive"))
      (node (ref "J1") (pin "79") (pinfunction "79_79") (pintype "passive"))
      (node (ref "J1") (pin "80") (pinfunction "80_80") (pintype "passive"))
      (node (ref "J1") (pin "99") (pinfunction "99_99") (pintype "passive"))
      (node (ref "J2") (pin "1") (pinfunction "0_1") (pintype "passive"))
      (node (ref "J2") (pin "2") (pinfunction "1_2") (pintype "passive"))
      (node (ref "J2") (pin "21") (pinfunction "21_21") (pintype "passive"))
      (node (ref "J2") (pin "22") (pinfunction "22_22") (pintype "passive"))
      (node (ref "J2") (pin "41") (pinfunction "41_41") (pintype "passive"))
      (node (ref "J2") (pin "42") (pinfunction "42_42") (pintype "passive"))
      (node (ref "J2") (pin "61") (pinfunction "61_61") (pintype "passive"))
      (node (ref "J2") (pin "62") (pinfunction "62_62") (pintype "passive"))
      (node (ref "J2") (pin "81") (pinfunction "81_81") (pintype "passive"))
      (node (ref "J2") (pin "82") (pinfunction "82_82") (pintype "passive"))
      (node (ref "R10") (pin "1") (pinfunction "0_1") (pintype "passive"))
      (node (ref "R14") (pin "1") (pinfunction "0_1") (pintype "passive"))
      (node (ref "R19") (pin "1") (pinfunction "0_1") (pintype "passive"))
      (node (ref "R2") (pin "1") (pinfunction "0_1") (pintype "passive"))
      (node (ref "R21") (pin "1") (pinfunction "0_1") (pintype "passive"))
      (node (ref "R6") (pin "1") (pinfunction "0_1") (pintype "passive"))
      (node (ref "U1") (pin "4") (pinfunction "GND_4") (pintype "power_in"))
      (node (ref "U1") (pin "6") (pinfunction "AGND_6") (pintype "power_in"))
      (node (ref "U2") (pin "4") (pinfunction "GND_4") (pintype "power_in"))
      (node (ref "U2") (pin "6") (pinfunction "AGND_6") (pintype "power_in"))
      (node (ref "U3") (pin "4") (pinfunction "GND_4") (pintype "power_in"))
      (node (ref "U3") (pin "6") (pinfunction "AGND_6") (pintype "power_in"))
      (node (ref "U4") (pin "2") (pinfunction "GND_2") (pintype "passive"))
      (node (ref "U5") (pin "4") (pinfunction "GND_4") (pintype "power_in"))
      (node (ref "U5") (pin "6") (pinfunction "AGND_6") (pintype "power_in"))
    )
    (net (code "208") (name "LVDS_IO") (class "Default")
      (node (ref "C15") (pin "1") (pinfunction "0_1") (pintype "passive"))
      (node (ref "R18") (pin "2") (pinfunction "2_2") (pintype "passive"))
      (node (ref "R20") (pin "2") (pinfunction "2_2") (pintype "passive"))
      (node (ref "U4") (pin "5") (pinfunction "OUT_5") (pintype "passive"))
    )
    (net (code "209") (name "Net-(J3-0)") (class "Default")
      (node (ref "J3") (pin "1") (pinfunction "0_1") (pintype "passive"))
      (node (ref "J3") (pin "3") (pinfunction "2_3") (pintype "passive"))
      (node (ref "R21") (pin "2") (pinfunction "2_2") (pintype "passive"))
      (node (ref "U4") (pin "4") (pinfunction "FB_4") (pintype "passive"))
    )
    (net (code "210") (name "Net-(J3-1)") (class "Default")
      (node (ref "J3") (pin "2") (pinfunction "1_2") (pintype "passive"))
      (node (ref "R18") (pin "1") (pinfunction "0_1") (pintype "passive"))
    )
    (net (code "211") (name "Net-(J3-3)") (class "Default")
      (node (ref "J3") (pin "4") (pinfunction "3_4") (pintype "passive"))
      (node (ref "R20") (pin "1") (pinfunction "0_1") (pintype "passive"))
    )
    (net (code "212") (name "Net-(L1-1)") (class "Default")
      (node (ref "L1") (pin "2") (pinfunction "1_2") (pintype "passive"))
      (node (ref "U1") (pin "3") (pinfunction "SW_3") (pintype "passive"))
    )
    (net (code "213") (name "Net-(L2-1)") (class "Default")
      (node (ref "L2") (pin "2") (pinfunction "1_2") (pintype "passive"))
      (node (ref "U2") (pin "3") (pinfunction "SW_3") (pintype "passive"))
    )
    (net (code "214") (name "Net-(L3-1)") (class "Default")
      (node (ref "L3") (pin "2") (pinfunction "1_2") (pintype "passive"))
      (node (ref "U3") (pin "3") (pinfunction "SW_3") (pintype "passive"))
    )
    (net (code "215") (name "Net-(L4-1)") (class "Default")
      (node (ref "L4") (pin "2") (pinfunction "1_2") (pintype "passive"))
      (node (ref "U5") (pin "3") (pinfunction "SW_3") (pintype "passive"))
    )
    (net (code "216") (name "Net-(R3-0)") (class "Default")
      (node (ref "R3") (pin "1") (pinfunction "0_1") (pintype "passive"))
      (node (ref "U1") (pin "1") (pinfunction "PG_1") (pintype "passive"))
    )
    (net (code "217") (name "Net-(R4-0)") (class "Default")
      (node (ref "R4") (pin "1") (pinfunction "0_1") (pintype "passive"))
      (node (ref "U1") (pin "8") (pinfunction "EN_8") (pintype "passive"))
    )
    (net (code "218") (name "Net-(R5-0)") (class "Default")
      (node (ref "R5") (pin "1") (pinfunction "0_1") (pintype "passive"))
      (node (ref "R6") (pin "2") (pinfunction "2_2") (pintype "passive"))
      (node (ref "U1") (pin "7") (pinfunction "FB_7") (pintype "passive"))
    )
    (net (code "219") (name "Net-(R7-0)") (class "Default")
      (node (ref "R7") (pin "1") (pinfunction "0_1") (pintype "passive"))
      (node (ref "U2") (pin "1") (pinfunction "PG_1") (pintype "passive"))
    )
    (net (code "220") (name "Net-(R8-0)") (class "Default")
      (node (ref "R8") (pin "1") (pinfunction "0_1") (pintype "passive"))
      (node (ref "U2") (pin "8") (pinfunction "EN_8") (pintype "passive"))
    )
    (net (code "221") (name "Net-(R9-0)") (class "Default")
      (node (ref "R10") (pin "2") (pinfunction "2_2") (pintype "passive"))
      (node (ref "R9") (pin "1") (pinfunction "0_1") (pintype "passive"))
      (node (ref "U2") (pin "7") (pinfunction "FB_7") (pintype "passive"))
    )
    (net (code "222") (name "Net-(R11-0)") (class "Default")
      (node (ref "R11") (pin "1") (pinfunction "0_1") (pintype "passive"))
      (node (ref "U3") (pin "1") (pinfunction "PG_1") (pintype "passive"))
    )
    (net (code "223") (name "Net-(R12-0)") (class "Default")
      (node (ref "R12") (pin "1") (pinfunction "0_1") (pintype "passive"))
      (node (ref "U3") (pin "8") (pinfunction "EN_8") (pintype "passive"))
    )
    (net (code "224") (name "Net-(R13-0)") (class "Default")
      (node (ref "R13") (pin "1") (pinfunction "0_1") (pintype "passive"))
      (node (ref "R14") (pin "2") (pinfunction "2_2") (pintype "passive"))
      (node (ref "U3") (pin "7") (pinfunction "FB_7") (pintype "passive"))
    )
    (net (code "225") (name "Net-(R15-0)") (class "Default")
      (node (ref "R15") (pin "1") (pinfunction "0_1") (pintype "passive"))
      (node (ref "U5") (pin "1") (pinfunction "PG_1") (pintype "passive"))
    )
    (net (code "226") (name "Net-(R16-0)") (class "Default")
      (node (ref "R16") (pin "1") (pinfunction "0_1") (pintype "passive"))
      (node (ref "U5") (pin "8") (pinfunction "EN_8") (pintype "passive"))
    )
    (net (code "227") (name "Net-(R17-0)") (class "Default")
      (node (ref "R17") (pin "1") (pinfunction "0_1") (pintype "passive"))
      (node (ref "R19") (pin "2") (pinfunction "2_2") (pintype "passive"))
      (node (ref "U5") (pin "7") (pinfunction "FB_7") (pintype "passive"))
    )
    (net (code "228") (name "PLLA2V5") (class "Default")
      (node (ref "B1") (pin "1") (pinfunction "0_1") (pintype "passive"))
      (node (ref "C3") (pin "1") (pinfunction "0_1") (pintype "passive"))
    )
    (net (code "229") (name "PLLD1V2") (class "Default")
      (node (ref "B2") (pin "1") (pinfunction "0_1") (pintype "passive"))
      (node (ref "C4") (pin "1") (pinfunction "0_1") (pintype "passive"))
    )
    (net (code "230") (name "USB5V0") (class "Default")
      (node (ref "C10") (pin "1") (pinfunction "0_1") (pintype "passive"))
      (node (ref "C13") (pin "1") (pinfunction "0_1") (pintype "passive"))
      (node (ref "C14") (pin "1") (pinfunction "0_1") (pintype "passive"))
      (node (ref "C18") (pin "1") (pinfunction "0_1") (pintype "passive"))
      (node (ref "C7") (pin "1") (pinfunction "0_1") (pintype "passive"))
      (node (ref "J1") (pin "1") (pinfunction "0_1") (pintype "passive"))
      (node (ref "J1") (pin "2") (pinfunction "1_2") (pintype "passive"))
      (node (ref "J1") (pin "3") (pinfunction "2_3") (pintype "passive"))
      (node (ref "J1") (pin "4") (pinfunction "3_4") (pintype "passive"))
      (node (ref "J2") (pin "100") (pinfunction "100_100") (pintype "passive"))
      (node (ref "J2") (pin "97") (pinfunction "97_97") (pintype "passive"))
      (node (ref "J2") (pin "98") (pinfunction "98_98") (pintype "passive"))
      (node (ref "J2") (pin "99") (pinfunction "99_99") (pintype "passive"))
      (node (ref "R11") (pin "2") (pinfunction "2_2") (pintype "passive"))
      (node (ref "R12") (pin "2") (pinfunction "2_2") (pintype "passive"))
      (node (ref "R15") (pin "2") (pinfunction "2_2") (pintype "passive"))
      (node (ref "R16") (pin "2") (pinfunction "2_2") (pintype "passive"))
      (node (ref "R3") (pin "2") (pinfunction "2_2") (pintype "passive"))
      (node (ref "R4") (pin "2") (pinfunction "2_2") (pintype "passive"))
      (node (ref "R7") (pin "2") (pinfunction "2_2") (pintype "passive"))
      (node (ref "R8") (pin "2") (pinfunction "2_2") (pintype "passive"))
      (node (ref "U1") (pin "2") (pinfunction "IN_2") (pintype "power_in"))
      (node (ref "U2") (pin "2") (pinfunction "IN_2") (pintype "power_in"))
      (node (ref "U3") (pin "2") (pinfunction "IN_2") (pintype "power_in"))
      (node (ref "U4") (pin "1") (pinfunction "IN_1") (pintype "passive"))
      (node (ref "U4") (pin "3") (pinfunction "EN_3") (pintype "passive"))
      (node (ref "U5") (pin "2") (pinfunction "IN_2") (pintype "power_in"))
    )
    (net (code "231") (name "unconnected-(J1-Pad28)") (class "Default")
      (node (ref "J1") (pin "28") (pinfunction "28_28") (pintype "passive+no_connect"))
    )
  )
)
